# fpgaB35.net
KiCad netlist of a schematic drawn in Altium Designer
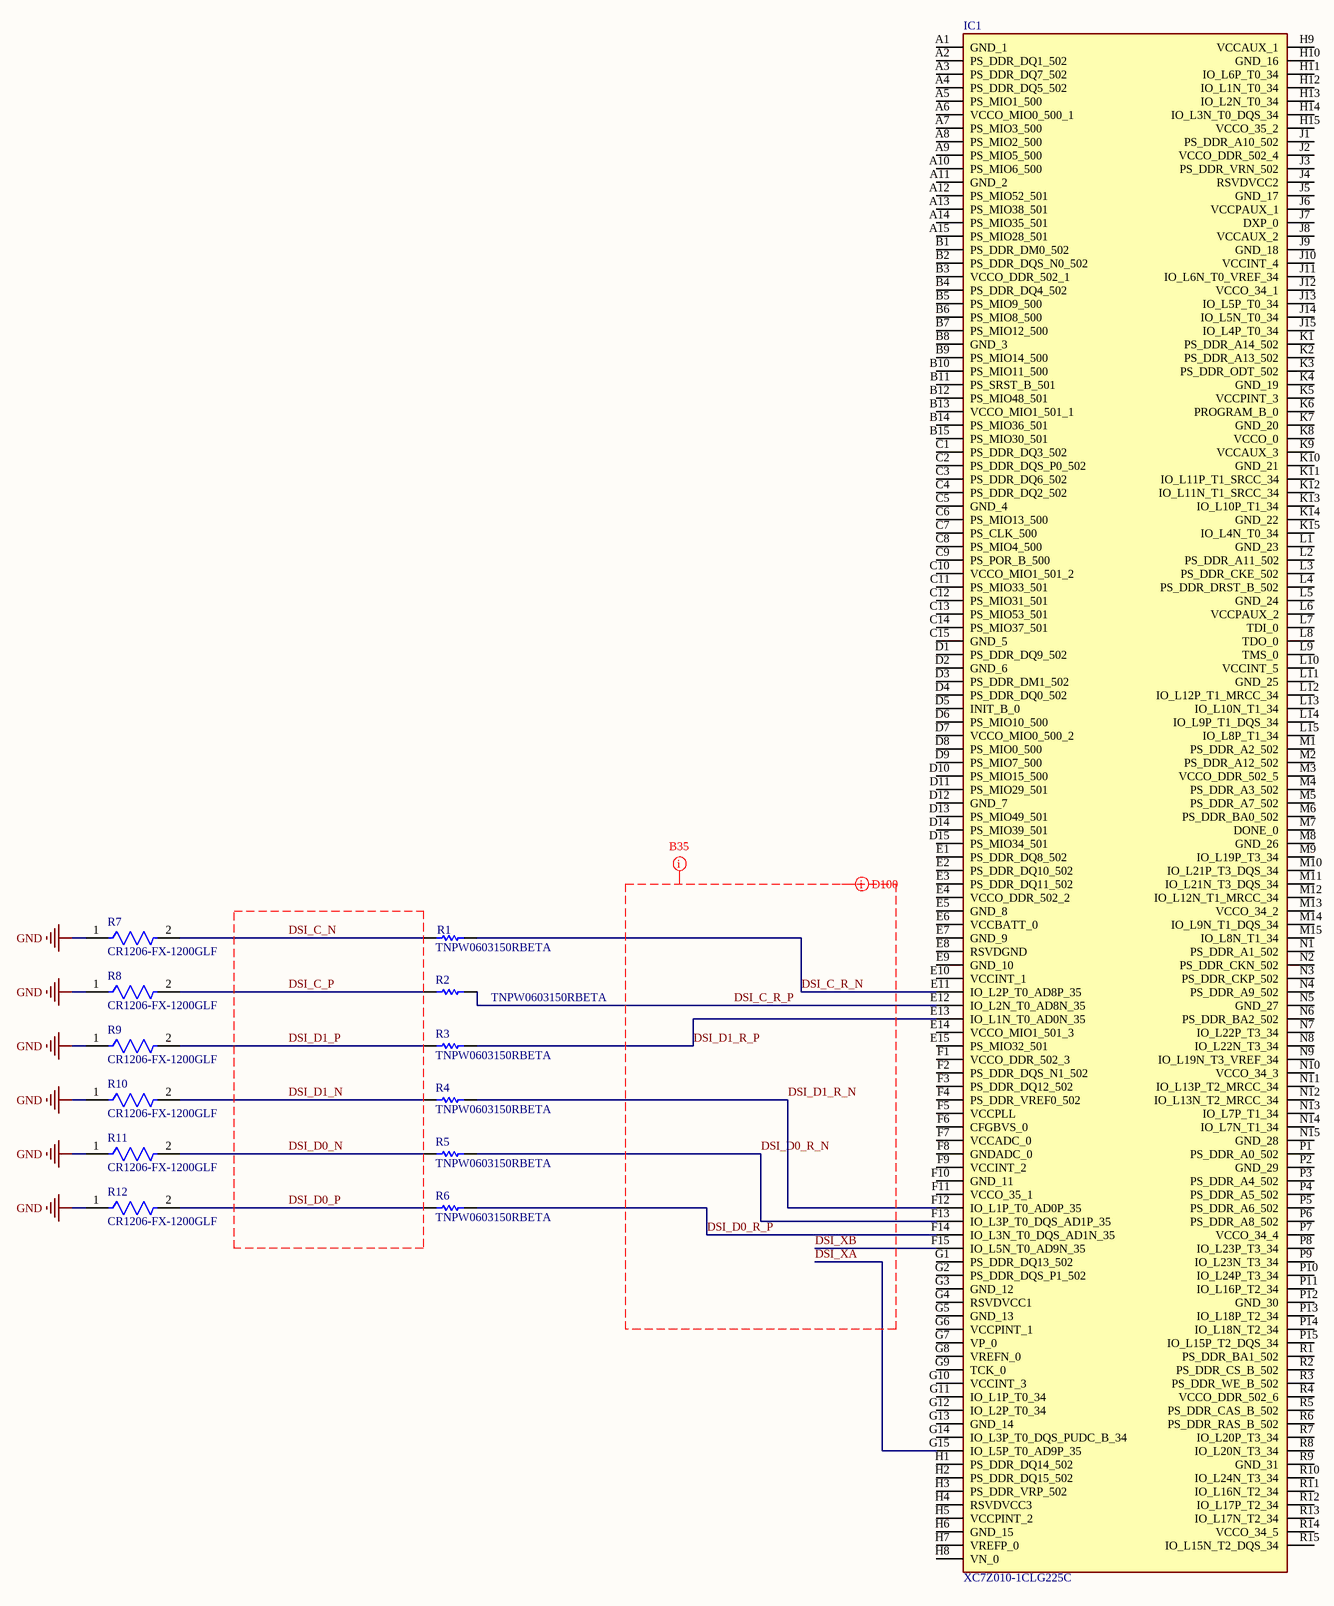
[diagram p0: fpgaB35.SchDoc]

(export (version "E")
  (design (tool "Eeschema 10.0.6"))
  (components
    (comp (ref "IC1")
      (value "XC7Z010-1CLG225C")
      (footprint "SamacSys:BGA225C80P15X15_1300X1300X140")
      (description "Integrated Circuit")
      (fields (field (name "MOUSER PART NUMBER") "217-XC7Z010-1CLG225C"))
      (libsource (lib "*") (part "XC7Z010-1CLG225C"))
    )
    (comp (ref "R1")
      (value "TNPW0603150RBETA")
      (footprint "RESC1609X55X30NL10T20")
      (fields (field (name "MANUFACTURER") "Vishay Dale"))
      (libsource (lib "Altium Content Vault") (part "RES"))
    )
    (comp (ref "R2")
      (value "TNPW0603150RBETA")
      (footprint "RESC1609X55X30NL10T20")
      (fields (field (name "MANUFACTURER") "Vishay Dale"))
      (libsource (lib "Altium Content Vault") (part "RES"))
    )
    (comp (ref "R3")
      (value "TNPW0603150RBETA")
      (footprint "RESC1609X55X30NL10T20")
      (fields (field (name "MANUFACTURER") "Vishay Dale"))
      (libsource (lib "Altium Content Vault") (part "RES"))
    )
    (comp (ref "R4")
      (value "TNPW0603150RBETA")
      (footprint "RESC1609X55X30NL10T20")
      (fields (field (name "MANUFACTURER") "Vishay Dale"))
      (libsource (lib "Altium Content Vault") (part "RES"))
    )
    (comp (ref "R5")
      (value "TNPW0603150RBETA")
      (footprint "RESC1609X55X30NL10T20")
      (fields (field (name "MANUFACTURER") "Vishay Dale"))
      (libsource (lib "Altium Content Vault") (part "RES"))
    )
    (comp (ref "R6")
      (value "TNPW0603150RBETA")
      (footprint "RESC1609X55X30NL10T20")
      (fields (field (name "MANUFACTURER") "Vishay Dale"))
      (libsource (lib "Altium Content Vault") (part "RES"))
    )
    (comp (ref "R7")
      (value "CR1206-FX-1200GLF")
      (footprint "FP-CR1206-MFG")
      (description "Thick Film Chip Resistors 1206 120Ω 0.25W 1% 100ppm/°C")
      (fields (field (name "TOLERANCE") "1%"))
      (libsource (lib "Altium Content Vault") (part "1029c3af85768c4190bb7ad29bc67b5"))
    )
    (comp (ref "R8")
      (value "CR1206-FX-1200GLF")
      (footprint "FP-CR1206-MFG")
      (description "Thick Film Chip Resistors 1206 120Ω 0.25W 1% 100ppm/°C")
      (fields (field (name "TOLERANCE") "1%"))
      (libsource (lib "Altium Content Vault") (part "1029c3af85768c4190bb7ad29bc67b5"))
    )
    (comp (ref "R9")
      (value "CR1206-FX-1200GLF")
      (footprint "FP-CR1206-MFG")
      (description "Thick Film Chip Resistors 1206 120Ω 0.25W 1% 100ppm/°C")
      (fields (field (name "TOLERANCE") "1%"))
      (libsource (lib "Altium Content Vault") (part "1029c3af85768c4190bb7ad29bc67b5"))
    )
    (comp (ref "R10")
      (value "CR1206-FX-1200GLF")
      (footprint "FP-CR1206-MFG")
      (description "Thick Film Chip Resistors 1206 120Ω 0.25W 1% 100ppm/°C")
      (fields (field (name "TOLERANCE") "1%"))
      (libsource (lib "Altium Content Vault") (part "1029c3af85768c4190bb7ad29bc67b5"))
    )
    (comp (ref "R11")
      (value "CR1206-FX-1200GLF")
      (footprint "FP-CR1206-MFG")
      (description "Thick Film Chip Resistors 1206 120Ω 0.25W 1% 100ppm/°C")
      (fields (field (name "TOLERANCE") "1%"))
      (libsource (lib "Altium Content Vault") (part "1029c3af85768c4190bb7ad29bc67b5"))
    )
    (comp (ref "R12")
      (value "CR1206-FX-1200GLF")
      (footprint "FP-CR1206-MFG")
      (description "Thick Film Chip Resistors 1206 120Ω 0.25W 1% 100ppm/°C")
      (fields (field (name "TOLERANCE") "1%"))
      (libsource (lib "Altium Content Vault") (part "1029c3af85768c4190bb7ad29bc67b5"))
    )
  )
  (nets
    (net (code "1") (name "/DSI_C_N") (class "Default")
      (node (ref "R1") (pin "1") (pinfunction "1_1") (pintype "passive"))
      (node (ref "R7") (pin "2") (pinfunction "2_2") (pintype "passive"))
    )
    (net (code "2") (name "/DSI_C_P") (class "Default")
      (node (ref "R2") (pin "1") (pinfunction "1_1") (pintype "passive"))
      (node (ref "R8") (pin "2") (pinfunction "2_2") (pintype "passive"))
    )
    (net (code "3") (name "/DSI_C_R_N") (class "Default")
      (node (ref "IC1") (pin "E11") (pinfunction "IO_L2P_T0_AD8P_35_E11") (pintype "passive"))
      (node (ref "R1") (pin "2") (pinfunction "2_2") (pintype "passive"))
    )
    (net (code "4") (name "/DSI_C_R_P") (class "Default")
      (node (ref "IC1") (pin "E12") (pinfunction "IO_L2N_T0_AD8N_35_E12") (pintype "passive"))
      (node (ref "R2") (pin "2") (pinfunction "2_2") (pintype "passive"))
    )
    (net (code "5") (name "/DSI_D0_N") (class "Default")
      (node (ref "R11") (pin "2") (pinfunction "2_2") (pintype "passive"))
      (node (ref "R5") (pin "1") (pinfunction "1_1") (pintype "passive"))
    )
    (net (code "6") (name "/DSI_D0_P") (class "Default")
      (node (ref "R12") (pin "2") (pinfunction "2_2") (pintype "passive"))
      (node (ref "R6") (pin "1") (pinfunction "1_1") (pintype "passive"))
    )
    (net (code "7") (name "/DSI_D0_R_N") (class "Default")
      (node (ref "IC1") (pin "F13") (pinfunction "IO_L3P_T0_DQS_AD1P_35_F13") (pintype "passive"))
      (node (ref "R5") (pin "2") (pinfunction "2_2") (pintype "passive"))
    )
    (net (code "8") (name "/DSI_D0_R_P") (class "Default")
      (node (ref "IC1") (pin "F14") (pinfunction "IO_L3N_T0_DQS_AD1N_35_F14") (pintype "passive"))
      (node (ref "R6") (pin "2") (pinfunction "2_2") (pintype "passive"))
    )
    (net (code "9") (name "/DSI_D1_N") (class "Default")
      (node (ref "R10") (pin "2") (pinfunction "2_2") (pintype "passive"))
      (node (ref "R4") (pin "1") (pinfunction "1_1") (pintype "passive"))
    )
    (net (code "10") (name "/DSI_D1_P") (class "Default")
      (node (ref "R3") (pin "1") (pinfunction "1_1") (pintype "passive"))
      (node (ref "R9") (pin "2") (pinfunction "2_2") (pintype "passive"))
    )
    (net (code "11") (name "/DSI_D1_R_N") (class "Default")
      (node (ref "IC1") (pin "F12") (pinfunction "IO_L1P_T0_AD0P_35_F12") (pintype "passive"))
      (node (ref "R4") (pin "2") (pinfunction "2_2") (pintype "passive"))
    )
    (net (code "12") (name "/DSI_D1_R_P") (class "Default")
      (node (ref "IC1") (pin "E13") (pinfunction "IO_L1N_T0_AD0N_35_E13") (pintype "passive"))
      (node (ref "R3") (pin "2") (pinfunction "2_2") (pintype "passive"))
    )
    (net (code "13") (name "/DSI_XA") (class "Default")
      (node (ref "IC1") (pin "G15") (pinfunction "IO_L5P_T0_AD9P_35_G15") (pintype "passive"))
    )
    (net (code "14") (name "/DSI_XB") (class "Default")
      (node (ref "IC1") (pin "F15") (pinfunction "IO_L5N_T0_AD9N_35_F15") (pintype "passive"))
    )
    (net (code "15") (name "GND") (class "Default")
      (node (ref "R10") (pin "1") (pinfunction "1_1") (pintype "passive"))
      (node (ref "R11") (pin "1") (pinfunction "1_1") (pintype "passive"))
      (node (ref "R12") (pin "1") (pinfunction "1_1") (pintype "passive"))
      (node (ref "R7") (pin "1") (pinfunction "1_1") (pintype "passive"))
      (node (ref "R8") (pin "1") (pinfunction "1_1") (pintype "passive"))
      (node (ref "R9") (pin "1") (pinfunction "1_1") (pintype "passive"))
    )
    (net (code "16") (name "unconnected-(IC1-CFGBVS_0-PadF6)") (class "Default")
      (node (ref "IC1") (pin "F6") (pinfunction "CFGBVS_0_F6") (pintype "passive"))
    )
    (net (code "17") (name "unconnected-(IC1-DONE_0-PadM7)") (class "Default")
      (node (ref "IC1") (pin "M7") (pinfunction "DONE_0_M7") (pintype "passive"))
    )
    (net (code "18") (name "unconnected-(IC1-DXP_0-PadJ7)") (class "Default")
      (node (ref "IC1") (pin "J7") (pinfunction "DXP_0_J7") (pintype "passive"))
    )
    (net (code "19") (name "unconnected-(IC1-GNDADC_0-PadF8)") (class "Default")
      (node (ref "IC1") (pin "F8") (pinfunction "GNDADC_0_F8") (pintype "passive"))
    )
    (net (code "20") (name "unconnected-(IC1-GND_1-PadA1)") (class "Default")
      (node (ref "IC1") (pin "A1") (pinfunction "GND_1_A1") (pintype "passive"))
    )
    (net (code "21") (name "unconnected-(IC1-GND_2-PadA11)") (class "Default")
      (node (ref "IC1") (pin "A11") (pinfunction "GND_2_A11") (pintype "passive"))
    )
    (net (code "22") (name "unconnected-(IC1-GND_3-PadB8)") (class "Default")
      (node (ref "IC1") (pin "B8") (pinfunction "GND_3_B8") (pintype "passive"))
    )
    (net (code "23") (name "unconnected-(IC1-GND_4-PadC5)") (class "Default")
      (node (ref "IC1") (pin "C5") (pinfunction "GND_4_C5") (pintype "passive"))
    )
    (net (code "24") (name "unconnected-(IC1-GND_5-PadC15)") (class "Default")
      (node (ref "IC1") (pin "C15") (pinfunction "GND_5_C15") (pintype "passive"))
    )
    (net (code "25") (name "unconnected-(IC1-GND_6-PadD2)") (class "Default")
      (node (ref "IC1") (pin "D2") (pinfunction "GND_6_D2") (pintype "passive"))
    )
    (net (code "26") (name "unconnected-(IC1-GND_7-PadD12)") (class "Default")
      (node (ref "IC1") (pin "D12") (pinfunction "GND_7_D12") (pintype "passive"))
    )
    (net (code "27") (name "unconnected-(IC1-GND_8-PadE5)") (class "Default")
      (node (ref "IC1") (pin "E5") (pinfunction "GND_8_E5") (pintype "passive"))
    )
    (net (code "28") (name "unconnected-(IC1-GND_9-PadE7)") (class "Default")
      (node (ref "IC1") (pin "E7") (pinfunction "GND_9_E7") (pintype "passive"))
    )
    (net (code "29") (name "unconnected-(IC1-GND_10-PadE9)") (class "Default")
      (node (ref "IC1") (pin "E9") (pinfunction "GND_10_E9") (pintype "passive"))
    )
    (net (code "30") (name "unconnected-(IC1-GND_11-PadF10)") (class "Default")
      (node (ref "IC1") (pin "F10") (pinfunction "GND_11_F10") (pintype "passive"))
    )
    (net (code "31") (name "unconnected-(IC1-GND_12-PadG3)") (class "Default")
      (node (ref "IC1") (pin "G3") (pinfunction "GND_12_G3") (pintype "passive"))
    )
    (net (code "32") (name "unconnected-(IC1-GND_13-PadG5)") (class "Default")
      (node (ref "IC1") (pin "G5") (pinfunction "GND_13_G5") (pintype "passive"))
    )
    (net (code "33") (name "unconnected-(IC1-GND_14-PadG13)") (class "Default")
      (node (ref "IC1") (pin "G13") (pinfunction "GND_14_G13") (pintype "passive"))
    )
    (net (code "34") (name "unconnected-(IC1-GND_15-PadH6)") (class "Default")
      (node (ref "IC1") (pin "H6") (pinfunction "GND_15_H6") (pintype "passive"))
    )
    (net (code "35") (name "unconnected-(IC1-GND_16-PadH10)") (class "Default")
      (node (ref "IC1") (pin "H10") (pinfunction "GND_16_H10") (pintype "passive"))
    )
    (net (code "36") (name "unconnected-(IC1-GND_17-PadJ5)") (class "Default")
      (node (ref "IC1") (pin "J5") (pinfunction "GND_17_J5") (pintype "passive"))
    )
    (net (code "37") (name "unconnected-(IC1-GND_18-PadJ9)") (class "Default")
      (node (ref "IC1") (pin "J9") (pinfunction "GND_18_J9") (pintype "passive"))
    )
    (net (code "38") (name "unconnected-(IC1-GND_19-PadK4)") (class "Default")
      (node (ref "IC1") (pin "K4") (pinfunction "GND_19_K4") (pintype "passive"))
    )
    (net (code "39") (name "unconnected-(IC1-GND_20-PadK7)") (class "Default")
      (node (ref "IC1") (pin "K7") (pinfunction "GND_20_K7") (pintype "passive"))
    )
    (net (code "40") (name "unconnected-(IC1-GND_21-PadK10)") (class "Default")
      (node (ref "IC1") (pin "K10") (pinfunction "GND_21_K10") (pintype "passive"))
    )
    (net (code "41") (name "unconnected-(IC1-GND_22-PadK14)") (class "Default")
      (node (ref "IC1") (pin "K14") (pinfunction "GND_22_K14") (pintype "passive"))
    )
    (net (code "42") (name "unconnected-(IC1-GND_23-PadL1)") (class "Default")
      (node (ref "IC1") (pin "L1") (pinfunction "GND_23_L1") (pintype "passive"))
    )
    (net (code "43") (name "unconnected-(IC1-GND_24-PadL5)") (class "Default")
      (node (ref "IC1") (pin "L5") (pinfunction "GND_24_L5") (pintype "passive"))
    )
    (net (code "44") (name "unconnected-(IC1-GND_25-PadL11)") (class "Default")
      (node (ref "IC1") (pin "L11") (pinfunction "GND_25_L11") (pintype "passive"))
    )
    (net (code "45") (name "unconnected-(IC1-GND_26-PadM8)") (class "Default")
      (node (ref "IC1") (pin "M8") (pinfunction "GND_26_M8") (pintype "passive"))
    )
    (net (code "46") (name "unconnected-(IC1-GND_27-PadN5)") (class "Default")
      (node (ref "IC1") (pin "N5") (pinfunction "GND_27_N5") (pintype "passive"))
    )
    (net (code "47") (name "unconnected-(IC1-GND_28-PadN15)") (class "Default")
      (node (ref "IC1") (pin "N15") (pinfunction "GND_28_N15") (pintype "passive"))
    )
    (net (code "48") (name "unconnected-(IC1-GND_29-PadP2)") (class "Default")
      (node (ref "IC1") (pin "P2") (pinfunction "GND_29_P2") (pintype "passive"))
    )
    (net (code "49") (name "unconnected-(IC1-GND_30-PadP12)") (class "Default")
      (node (ref "IC1") (pin "P12") (pinfunction "GND_30_P12") (pintype "passive"))
    )
    (net (code "50") (name "unconnected-(IC1-GND_31-PadR9)") (class "Default")
      (node (ref "IC1") (pin "R9") (pinfunction "GND_31_R9") (pintype "passive"))
    )
    (net (code "51") (name "unconnected-(IC1-INIT_B_0-PadD5)") (class "Default")
      (node (ref "IC1") (pin "D5") (pinfunction "INIT_B_0_D5") (pintype "passive"))
    )
    (net (code "52") (name "unconnected-(IC1-IO_L1N_T0_34-PadH12)") (class "Default")
      (node (ref "IC1") (pin "H12") (pinfunction "IO_L1N_T0_34_H12") (pintype "passive"))
    )
    (net (code "53") (name "unconnected-(IC1-IO_L1P_T0_34-PadG11)") (class "Default")
      (node (ref "IC1") (pin "G11") (pinfunction "IO_L1P_T0_34_G11") (pintype "passive"))
    )
    (net (code "54") (name "unconnected-(IC1-IO_L2N_T0_34-PadH13)") (class "Default")
      (node (ref "IC1") (pin "H13") (pinfunction "IO_L2N_T0_34_H13") (pintype "passive"))
    )
    (net (code "55") (name "unconnected-(IC1-IO_L2P_T0_34-PadG12)") (class "Default")
      (node (ref "IC1") (pin "G12") (pinfunction "IO_L2P_T0_34_G12") (pintype "passive"))
    )
    (net (code "56") (name "unconnected-(IC1-IO_L3N_T0_DQS_34-PadH14)") (class "Default")
      (node (ref "IC1") (pin "H14") (pinfunction "IO_L3N_T0_DQS_34_H14") (pintype "passive"))
    )
    (net (code "57") (name "unconnected-(IC1-IO_L3P_T0_DQS_PUDC_B_34-PadG14)") (class "Default")
      (node (ref "IC1") (pin "G14") (pinfunction "IO_L3P_T0_DQS_PUDC_B_34_G14") (pintype "passive"))
    )
    (net (code "58") (name "unconnected-(IC1-IO_L4N_T0_34-PadK15)") (class "Default")
      (node (ref "IC1") (pin "K15") (pinfunction "IO_L4N_T0_34_K15") (pintype "passive"))
    )
    (net (code "59") (name "unconnected-(IC1-IO_L4P_T0_34-PadJ15)") (class "Default")
      (node (ref "IC1") (pin "J15") (pinfunction "IO_L4P_T0_34_J15") (pintype "passive"))
    )
    (net (code "60") (name "unconnected-(IC1-IO_L5N_T0_34-PadJ14)") (class "Default")
      (node (ref "IC1") (pin "J14") (pinfunction "IO_L5N_T0_34_J14") (pintype "passive"))
    )
    (net (code "61") (name "unconnected-(IC1-IO_L5P_T0_34-PadJ13)") (class "Default")
      (node (ref "IC1") (pin "J13") (pinfunction "IO_L5P_T0_34_J13") (pintype "passive"))
    )
    (net (code "62") (name "unconnected-(IC1-IO_L6N_T0_VREF_34-PadJ11)") (class "Default")
      (node (ref "IC1") (pin "J11") (pinfunction "IO_L6N_T0_VREF_34_J11") (pintype "passive"))
    )
    (net (code "63") (name "unconnected-(IC1-IO_L6P_T0_34-PadH11)") (class "Default")
      (node (ref "IC1") (pin "H11") (pinfunction "IO_L6P_T0_34_H11") (pintype "passive"))
    )
    (net (code "64") (name "unconnected-(IC1-IO_L7N_T1_34-PadN14)") (class "Default")
      (node (ref "IC1") (pin "N14") (pinfunction "IO_L7N_T1_34_N14") (pintype "passive"))
    )
    (net (code "65") (name "unconnected-(IC1-IO_L7P_T1_34-PadN13)") (class "Default")
      (node (ref "IC1") (pin "N13") (pinfunction "IO_L7P_T1_34_N13") (pintype "passive"))
    )
    (net (code "66") (name "unconnected-(IC1-IO_L8N_T1_34-PadM15)") (class "Default")
      (node (ref "IC1") (pin "M15") (pinfunction "IO_L8N_T1_34_M15") (pintype "passive"))
    )
    (net (code "67") (name "unconnected-(IC1-IO_L8P_T1_34-PadL15)") (class "Default")
      (node (ref "IC1") (pin "L15") (pinfunction "IO_L8P_T1_34_L15") (pintype "passive"))
    )
    (net (code "68") (name "unconnected-(IC1-IO_L9N_T1_DQS_34-PadM14)") (class "Default")
      (node (ref "IC1") (pin "M14") (pinfunction "IO_L9N_T1_DQS_34_M14") (pintype "passive"))
    )
    (net (code "69") (name "unconnected-(IC1-IO_L9P_T1_DQS_34-PadL14)") (class "Default")
      (node (ref "IC1") (pin "L14") (pinfunction "IO_L9P_T1_DQS_34_L14") (pintype "passive"))
    )
    (net (code "70") (name "unconnected-(IC1-IO_L10N_T1_34-PadL13)") (class "Default")
      (node (ref "IC1") (pin "L13") (pinfunction "IO_L10N_T1_34_L13") (pintype "passive"))
    )
    (net (code "71") (name "unconnected-(IC1-IO_L10P_T1_34-PadK13)") (class "Default")
      (node (ref "IC1") (pin "K13") (pinfunction "IO_L10P_T1_34_K13") (pintype "passive"))
    )
    (net (code "72") (name "unconnected-(IC1-IO_L11N_T1_SRCC_34-PadK12)") (class "Default")
      (node (ref "IC1") (pin "K12") (pinfunction "IO_L11N_T1_SRCC_34_K12") (pintype "passive"))
    )
    (net (code "73") (name "unconnected-(IC1-IO_L11P_T1_SRCC_34-PadK11)") (class "Default")
      (node (ref "IC1") (pin "K11") (pinfunction "IO_L11P_T1_SRCC_34_K11") (pintype "passive"))
    )
    (net (code "74") (name "unconnected-(IC1-IO_L12N_T1_MRCC_34-PadM12)") (class "Default")
      (node (ref "IC1") (pin "M12") (pinfunction "IO_L12N_T1_MRCC_34_M12") (pintype "passive"))
    )
    (net (code "75") (name "unconnected-(IC1-IO_L12P_T1_MRCC_34-PadL12)") (class "Default")
      (node (ref "IC1") (pin "L12") (pinfunction "IO_L12P_T1_MRCC_34_L12") (pintype "passive"))
    )
    (net (code "76") (name "unconnected-(IC1-IO_L13N_T2_MRCC_34-PadN12)") (class "Default")
      (node (ref "IC1") (pin "N12") (pinfunction "IO_L13N_T2_MRCC_34_N12") (pintype "passive"))
    )
    (net (code "77") (name "unconnected-(IC1-IO_L13P_T2_MRCC_34-PadN11)") (class "Default")
      (node (ref "IC1") (pin "N11") (pinfunction "IO_L13P_T2_MRCC_34_N11") (pintype "passive"))
    )
    (net (code "78") (name "unconnected-(IC1-IO_L15N_T2_DQS_34-PadR15)") (class "Default")
      (node (ref "IC1") (pin "R15") (pinfunction "IO_L15N_T2_DQS_34_R15") (pintype "passive"))
    )
    (net (code "79") (name "unconnected-(IC1-IO_L15P_T2_DQS_34-PadP15)") (class "Default")
      (node (ref "IC1") (pin "P15") (pinfunction "IO_L15P_T2_DQS_34_P15") (pintype "passive"))
    )
    (net (code "80") (name "unconnected-(IC1-IO_L16N_T2_34-PadR11)") (class "Default")
      (node (ref "IC1") (pin "R11") (pinfunction "IO_L16N_T2_34_R11") (pintype "passive"))
    )
    (net (code "81") (name "unconnected-(IC1-IO_L16P_T2_34-PadP11)") (class "Default")
      (node (ref "IC1") (pin "P11") (pinfunction "IO_L16P_T2_34_P11") (pintype "passive"))
    )
    (net (code "82") (name "unconnected-(IC1-IO_L17N_T2_34-PadR13)") (class "Default")
      (node (ref "IC1") (pin "R13") (pinfunction "IO_L17N_T2_34_R13") (pintype "passive"))
    )
    (net (code "83") (name "unconnected-(IC1-IO_L17P_T2_34-PadR12)") (class "Default")
      (node (ref "IC1") (pin "R12") (pinfunction "IO_L17P_T2_34_R12") (pintype "passive"))
    )
    (net (code "84") (name "unconnected-(IC1-IO_L18N_T2_34-PadP14)") (class "Default")
      (node (ref "IC1") (pin "P14") (pinfunction "IO_L18N_T2_34_P14") (pintype "passive"))
    )
    (net (code "85") (name "unconnected-(IC1-IO_L18P_T2_34-PadP13)") (class "Default")
      (node (ref "IC1") (pin "P13") (pinfunction "IO_L18P_T2_34_P13") (pintype "passive"))
    )
    (net (code "86") (name "unconnected-(IC1-IO_L19N_T3_VREF_34-PadN9)") (class "Default")
      (node (ref "IC1") (pin "N9") (pinfunction "IO_L19N_T3_VREF_34_N9") (pintype "passive"))
    )
    (net (code "87") (name "unconnected-(IC1-IO_L19P_T3_34-PadM9)") (class "Default")
      (node (ref "IC1") (pin "M9") (pinfunction "IO_L19P_T3_34_M9") (pintype "passive"))
    )
    (net (code "88") (name "unconnected-(IC1-IO_L20N_T3_34-PadR8)") (class "Default")
      (node (ref "IC1") (pin "R8") (pinfunction "IO_L20N_T3_34_R8") (pintype "passive"))
    )
    (net (code "89") (name "unconnected-(IC1-IO_L20P_T3_34-PadR7)") (class "Default")
      (node (ref "IC1") (pin "R7") (pinfunction "IO_L20P_T3_34_R7") (pintype "passive"))
    )
    (net (code "90") (name "unconnected-(IC1-IO_L21N_T3_DQS_34-PadM11)") (class "Default")
      (node (ref "IC1") (pin "M11") (pinfunction "IO_L21N_T3_DQS_34_M11") (pintype "passive"))
    )
    (net (code "91") (name "unconnected-(IC1-IO_L21P_T3_DQS_34-PadM10)") (class "Default")
      (node (ref "IC1") (pin "M10") (pinfunction "IO_L21P_T3_DQS_34_M10") (pintype "passive"))
    )
    (net (code "92") (name "unconnected-(IC1-IO_L22N_T3_34-PadN8)") (class "Default")
      (node (ref "IC1") (pin "N8") (pinfunction "IO_L22N_T3_34_N8") (pintype "passive"))
    )
    (net (code "93") (name "unconnected-(IC1-IO_L22P_T3_34-PadN7)") (class "Default")
      (node (ref "IC1") (pin "N7") (pinfunction "IO_L22P_T3_34_N7") (pintype "passive"))
    )
    (net (code "94") (name "unconnected-(IC1-IO_L23N_T3_34-PadP9)") (class "Default")
      (node (ref "IC1") (pin "P9") (pinfunction "IO_L23N_T3_34_P9") (pintype "passive"))
    )
    (net (code "95") (name "unconnected-(IC1-IO_L23P_T3_34-PadP8)") (class "Default")
      (node (ref "IC1") (pin "P8") (pinfunction "IO_L23P_T3_34_P8") (pintype "passive"))
    )
    (net (code "96") (name "unconnected-(IC1-IO_L24N_T3_34-PadR10)") (class "Default")
      (node (ref "IC1") (pin "R10") (pinfunction "IO_L24N_T3_34_R10") (pintype "passive"))
    )
    (net (code "97") (name "unconnected-(IC1-IO_L24P_T3_34-PadP10)") (class "Default")
      (node (ref "IC1") (pin "P10") (pinfunction "IO_L24P_T3_34_P10") (pintype "passive"))
    )
    (net (code "98") (name "unconnected-(IC1-PROGRAM_B_0-PadK6)") (class "Default")
      (node (ref "IC1") (pin "K6") (pinfunction "PROGRAM_B_0_K6") (pintype "passive"))
    )
    (net (code "99") (name "unconnected-(IC1-PS_CLK_500-PadC7)") (class "Default")
      (node (ref "IC1") (pin "C7") (pinfunction "PS_CLK_500_C7") (pintype "passive"))
    )
    (net (code "100") (name "unconnected-(IC1-PS_DDR_A0_502-PadP1)") (class "Default")
      (node (ref "IC1") (pin "P1") (pinfunction "PS_DDR_A0_502_P1") (pintype "passive"))
    )
    (net (code "101") (name "unconnected-(IC1-PS_DDR_A1_502-PadN1)") (class "Default")
      (node (ref "IC1") (pin "N1") (pinfunction "PS_DDR_A1_502_N1") (pintype "passive"))
    )
    (net (code "102") (name "unconnected-(IC1-PS_DDR_A2_502-PadM1)") (class "Default")
      (node (ref "IC1") (pin "M1") (pinfunction "PS_DDR_A2_502_M1") (pintype "passive"))
    )
    (net (code "103") (name "unconnected-(IC1-PS_DDR_A3_502-PadM4)") (class "Default")
      (node (ref "IC1") (pin "M4") (pinfunction "PS_DDR_A3_502_M4") (pintype "passive"))
    )
    (net (code "104") (name "unconnected-(IC1-PS_DDR_A4_502-PadP3)") (class "Default")
      (node (ref "IC1") (pin "P3") (pinfunction "PS_DDR_A4_502_P3") (pintype "passive"))
    )
    (net (code "105") (name "unconnected-(IC1-PS_DDR_A5_502-PadP4)") (class "Default")
      (node (ref "IC1") (pin "P4") (pinfunction "PS_DDR_A5_502_P4") (pintype "passive"))
    )
    (net (code "106") (name "unconnected-(IC1-PS_DDR_A6_502-PadP5)") (class "Default")
      (node (ref "IC1") (pin "P5") (pinfunction "PS_DDR_A6_502_P5") (pintype "passive"))
    )
    (net (code "107") (name "unconnected-(IC1-PS_DDR_A7_502-PadM5)") (class "Default")
      (node (ref "IC1") (pin "M5") (pinfunction "PS_DDR_A7_502_M5") (pintype "passive"))
    )
    (net (code "108") (name "unconnected-(IC1-PS_DDR_A8_502-PadP6)") (class "Default")
      (node (ref "IC1") (pin "P6") (pinfunction "PS_DDR_A8_502_P6") (pintype "passive"))
    )
    (net (code "109") (name "unconnected-(IC1-PS_DDR_A9_502-PadN4)") (class "Default")
      (node (ref "IC1") (pin "N4") (pinfunction "PS_DDR_A9_502_N4") (pintype "passive"))
    )
    (net (code "110") (name "unconnected-(IC1-PS_DDR_A10_502-PadJ1)") (class "Default")
      (node (ref "IC1") (pin "J1") (pinfunction "PS_DDR_A10_502_J1") (pintype "passive"))
    )
    (net (code "111") (name "unconnected-(IC1-PS_DDR_A11_502-PadL2)") (class "Default")
      (node (ref "IC1") (pin "L2") (pinfunction "PS_DDR_A11_502_L2") (pintype "passive"))
    )
    (net (code "112") (name "unconnected-(IC1-PS_DDR_A12_502-PadM2)") (class "Default")
      (node (ref "IC1") (pin "M2") (pinfunction "PS_DDR_A12_502_M2") (pintype "passive"))
    )
    (net (code "113") (name "unconnected-(IC1-PS_DDR_A13_502-PadK2)") (class "Default")
      (node (ref "IC1") (pin "K2") (pinfunction "PS_DDR_A13_502_K2") (pintype "passive"))
    )
    (net (code "114") (name "unconnected-(IC1-PS_DDR_A14_502-PadK1)") (class "Default")
      (node (ref "IC1") (pin "K1") (pinfunction "PS_DDR_A14_502_K1") (pintype "passive"))
    )
    (net (code "115") (name "unconnected-(IC1-PS_DDR_BA0_502-PadM6)") (class "Default")
      (node (ref "IC1") (pin "M6") (pinfunction "PS_DDR_BA0_502_M6") (pintype "passive"))
    )
    (net (code "116") (name "unconnected-(IC1-PS_DDR_BA1_502-PadR1)") (class "Default")
      (node (ref "IC1") (pin "R1") (pinfunction "PS_DDR_BA1_502_R1") (pintype "passive"))
    )
    (net (code "117") (name "unconnected-(IC1-PS_DDR_BA2_502-PadN6)") (class "Default")
      (node (ref "IC1") (pin "N6") (pinfunction "PS_DDR_BA2_502_N6") (pintype "passive"))
    )
    (net (code "118") (name "unconnected-(IC1-PS_DDR_CAS_B_502-PadR5)") (class "Default")
      (node (ref "IC1") (pin "R5") (pinfunction "PS_DDR_CAS_B_502_R5") (pintype "passive"))
    )
    (net (code "119") (name "unconnected-(IC1-PS_DDR_CKE_502-PadL3)") (class "Default")
      (node (ref "IC1") (pin "L3") (pinfunction "PS_DDR_CKE_502_L3") (pintype "passive"))
    )
    (net (code "120") (name "unconnected-(IC1-PS_DDR_CKN_502-PadN2)") (class "Default")
      (node (ref "IC1") (pin "N2") (pinfunction "PS_DDR_CKN_502_N2") (pintype "passive"))
    )
    (net (code "121") (name "unconnected-(IC1-PS_DDR_CKP_502-PadN3)") (class "Default")
      (node (ref "IC1") (pin "N3") (pinfunction "PS_DDR_CKP_502_N3") (pintype "passive"))
    )
    (net (code "122") (name "unconnected-(IC1-PS_DDR_CS_B_502-PadR2)") (class "Default")
      (node (ref "IC1") (pin "R2") (pinfunction "PS_DDR_CS_B_502_R2") (pintype "passive"))
    )
    (net (code "123") (name "unconnected-(IC1-PS_DDR_DM0_502-PadB1)") (class "Default")
      (node (ref "IC1") (pin "B1") (pinfunction "PS_DDR_DM0_502_B1") (pintype "passive"))
    )
    (net (code "124") (name "unconnected-(IC1-PS_DDR_DM1_502-PadD3)") (class "Default")
      (node (ref "IC1") (pin "D3") (pinfunction "PS_DDR_DM1_502_D3") (pintype "passive"))
    )
    (net (code "125") (name "unconnected-(IC1-PS_DDR_DQ0_502-PadD4)") (class "Default")
      (node (ref "IC1") (pin "D4") (pinfunction "PS_DDR_DQ0_502_D4") (pintype "passive"))
    )
    (net (code "126") (name "unconnected-(IC1-PS_DDR_DQ1_502-PadA2)") (class "Default")
      (node (ref "IC1") (pin "A2") (pinfunction "PS_DDR_DQ1_502_A2") (pintype "passive"))
    )
    (net (code "127") (name "unconnected-(IC1-PS_DDR_DQ2_502-PadC4)") (class "Default")
      (node (ref "IC1") (pin "C4") (pinfunction "PS_DDR_DQ2_502_C4") (pintype "passive"))
    )
    (net (code "128") (name "unconnected-(IC1-PS_DDR_DQ3_502-PadC1)") (class "Default")
      (node (ref "IC1") (pin "C1") (pinfunction "PS_DDR_DQ3_502_C1") (pintype "passive"))
    )
    (net (code "129") (name "unconnected-(IC1-PS_DDR_DQ4_502-PadB4)") (class "Default")
      (node (ref "IC1") (pin "B4") (pinfunction "PS_DDR_DQ4_502_B4") (pintype "passive"))
    )
    (net (code "130") (name "unconnected-(IC1-PS_DDR_DQ5_502-PadA4)") (class "Default")
      (node (ref "IC1") (pin "A4") (pinfunction "PS_DDR_DQ5_502_A4") (pintype "passive"))
    )
    (net (code "131") (name "unconnected-(IC1-PS_DDR_DQ6_502-PadC3)") (class "Default")
      (node (ref "IC1") (pin "C3") (pinfunction "PS_DDR_DQ6_502_C3") (pintype "passive"))
    )
    (net (code "132") (name "unconnected-(IC1-PS_DDR_DQ7_502-PadA3)") (class "Default")
      (node (ref "IC1") (pin "A3") (pinfunction "PS_DDR_DQ7_502_A3") (pintype "passive"))
    )
    (net (code "133") (name "unconnected-(IC1-PS_DDR_DQ8_502-PadE1)") (class "Default")
      (node (ref "IC1") (pin "E1") (pinfunction "PS_DDR_DQ8_502_E1") (pintype "passive"))
    )
    (net (code "134") (name "unconnected-(IC1-PS_DDR_DQ9_502-PadD1)") (class "Default")
      (node (ref "IC1") (pin "D1") (pinfunction "PS_DDR_DQ9_502_D1") (pintype "passive"))
    )
    (net (code "135") (name "unconnected-(IC1-PS_DDR_DQ10_502-PadE2)") (class "Default")
      (node (ref "IC1") (pin "E2") (pinfunction "PS_DDR_DQ10_502_E2") (pintype "passive"))
    )
    (net (code "136") (name "unconnected-(IC1-PS_DDR_DQ11_502-PadE3)") (class "Default")
      (node (ref "IC1") (pin "E3") (pinfunction "PS_DDR_DQ11_502_E3") (pintype "passive"))
    )
    (net (code "137") (name "unconnected-(IC1-PS_DDR_DQ12_502-PadF3)") (class "Default")
      (node (ref "IC1") (pin "F3") (pinfunction "PS_DDR_DQ12_502_F3") (pintype "passive"))
    )
    (net (code "138") (name "unconnected-(IC1-PS_DDR_DQ13_502-PadG1)") (class "Default")
      (node (ref "IC1") (pin "G1") (pinfunction "PS_DDR_DQ13_502_G1") (pintype "passive"))
    )
    (net (code "139") (name "unconnected-(IC1-PS_DDR_DQ14_502-PadH1)") (class "Default")
      (node (ref "IC1") (pin "H1") (pinfunction "PS_DDR_DQ14_502_H1") (pintype "passive"))
    )
    (net (code "140") (name "unconnected-(IC1-PS_DDR_DQ15_502-PadH2)") (class "Default")
      (node (ref "IC1") (pin "H2") (pinfunction "PS_DDR_DQ15_502_H2") (pintype "passive"))
    )
    (net (code "141") (name "unconnected-(IC1-PS_DDR_DQS_N0_502-PadB2)") (class "Default")
      (node (ref "IC1") (pin "B2") (pinfunction "PS_DDR_DQS_N0_502_B2") (pintype "passive"))
    )
    (net (code "142") (name "unconnected-(IC1-PS_DDR_DQS_N1_502-PadF2)") (class "Default")
      (node (ref "IC1") (pin "F2") (pinfunction "PS_DDR_DQS_N1_502_F2") (pintype "passive"))
    )
    (net (code "143") (name "unconnected-(IC1-PS_DDR_DQS_P0_502-PadC2)") (class "Default")
      (node (ref "IC1") (pin "C2") (pinfunction "PS_DDR_DQS_P0_502_C2") (pintype "passive"))
    )
    (net (code "144") (name "unconnected-(IC1-PS_DDR_DQS_P1_502-PadG2)") (class "Default")
      (node (ref "IC1") (pin "G2") (pinfunction "PS_DDR_DQS_P1_502_G2") (pintype "passive"))
    )
    (net (code "145") (name "unconnected-(IC1-PS_DDR_DRST_B_502-PadL4)") (class "Default")
      (node (ref "IC1") (pin "L4") (pinfunction "PS_DDR_DRST_B_502_L4") (pintype "passive"))
    )
    (net (code "146") (name "unconnected-(IC1-PS_DDR_ODT_502-PadK3)") (class "Default")
      (node (ref "IC1") (pin "K3") (pinfunction "PS_DDR_ODT_502_K3") (pintype "passive"))
    )
    (net (code "147") (name "unconnected-(IC1-PS_DDR_RAS_B_502-PadR6)") (class "Default")
      (node (ref "IC1") (pin "R6") (pinfunction "PS_DDR_RAS_B_502_R6") (pintype "passive"))
    )
    (net (code "148") (name "unconnected-(IC1-PS_DDR_VREF0_502-PadF4)") (class "Default")
      (node (ref "IC1") (pin "F4") (pinfunction "PS_DDR_VREF0_502_F4") (pintype "passive"))
    )
    (net (code "149") (name "unconnected-(IC1-PS_DDR_VRN_502-PadJ3)") (class "Default")
      (node (ref "IC1") (pin "J3") (pinfunction "PS_DDR_VRN_502_J3") (pintype "passive"))
    )
    (net (code "150") (name "unconnected-(IC1-PS_DDR_VRP_502-PadH3)") (class "Default")
      (node (ref "IC1") (pin "H3") (pinfunction "PS_DDR_VRP_502_H3") (pintype "passive"))
    )
    (net (code "151") (name "unconnected-(IC1-PS_DDR_WE_B_502-PadR3)") (class "Default")
      (node (ref "IC1") (pin "R3") (pinfunction "PS_DDR_WE_B_502_R3") (pintype "passive"))
    )
    (net (code "152") (name "unconnected-(IC1-PS_MIO0_500-PadD8)") (class "Default")
      (node (ref "IC1") (pin "D8") (pinfunction "PS_MIO0_500_D8") (pintype "passive"))
    )
    (net (code "153") (name "unconnected-(IC1-PS_MIO1_500-PadA5)") (class "Default")
      (node (ref "IC1") (pin "A5") (pinfunction "PS_MIO1_500_A5") (pintype "passive"))
    )
    (net (code "154") (name "unconnected-(IC1-PS_MIO2_500-PadA8)") (class "Default")
      (node (ref "IC1") (pin "A8") (pinfunction "PS_MIO2_500_A8") (pintype "passive"))
    )
    (net (code "155") (name "unconnected-(IC1-PS_MIO3_500-PadA7)") (class "Default")
      (node (ref "IC1") (pin "A7") (pinfunction "PS_MIO3_500_A7") (pintype "passive"))
    )
    (net (code "156") (name "unconnected-(IC1-PS_MIO4_500-PadC8)") (class "Default")
      (node (ref "IC1") (pin "C8") (pinfunction "PS_MIO4_500_C8") (pintype "passive"))
    )
    (net (code "157") (name "unconnected-(IC1-PS_MIO5_500-PadA9)") (class "Default")
      (node (ref "IC1") (pin "A9") (pinfunction "PS_MIO5_500_A9") (pintype "passive"))
    )
    (net (code "158") (name "unconnected-(IC1-PS_MIO6_500-PadA10)") (class "Default")
      (node (ref "IC1") (pin "A10") (pinfunction "PS_MIO6_500_A10") (pintype "passive"))
    )
    (net (code "159") (name "unconnected-(IC1-PS_MIO7_500-PadD9)") (class "Default")
      (node (ref "IC1") (pin "D9") (pinfunction "PS_MIO7_500_D9") (pintype "passive"))
    )
    (net (code "160") (name "unconnected-(IC1-PS_MIO8_500-PadB6)") (class "Default")
      (node (ref "IC1") (pin "B6") (pinfunction "PS_MIO8_500_B6") (pintype "passive"))
    )
    (net (code "161") (name "unconnected-(IC1-PS_MIO9_500-PadB5)") (class "Default")
      (node (ref "IC1") (pin "B5") (pinfunction "PS_MIO9_500_B5") (pintype "passive"))
    )
    (net (code "162") (name "unconnected-(IC1-PS_MIO10_500-PadD6)") (class "Default")
      (node (ref "IC1") (pin "D6") (pinfunction "PS_MIO10_500_D6") (pintype "passive"))
    )
    (net (code "163") (name "unconnected-(IC1-PS_MIO11_500-PadB10)") (class "Default")
      (node (ref "IC1") (pin "B10") (pinfunction "PS_MIO11_500_B10") (pintype "passive"))
    )
    (net (code "164") (name "unconnected-(IC1-PS_MIO12_500-PadB7)") (class "Default")
      (node (ref "IC1") (pin "B7") (pinfunction "PS_MIO12_500_B7") (pintype "passive"))
    )
    (net (code "165") (name "unconnected-(IC1-PS_MIO13_500-PadC6)") (class "Default")
      (node (ref "IC1") (pin "C6") (pinfunction "PS_MIO13_500_C6") (pintype "passive"))
    )
    (net (code "166") (name "unconnected-(IC1-PS_MIO14_500-PadB9)") (class "Default")
      (node (ref "IC1") (pin "B9") (pinfunction "PS_MIO14_500_B9") (pintype "passive"))
    )
    (net (code "167") (name "unconnected-(IC1-PS_MIO15_500-PadD10)") (class "Default")
      (node (ref "IC1") (pin "D10") (pinfunction "PS_MIO15_500_D10") (pintype "passive"))
    )
    (net (code "168") (name "unconnected-(IC1-PS_MIO28_501-PadA15)") (class "Default")
      (node (ref "IC1") (pin "A15") (pinfunction "PS_MIO28_501_A15") (pintype "passive"))
    )
    (net (code "169") (name "unconnected-(IC1-PS_MIO29_501-PadD11)") (class "Default")
      (node (ref "IC1") (pin "D11") (pinfunction "PS_MIO29_501_D11") (pintype "passive"))
    )
    (net (code "170") (name "unconnected-(IC1-PS_MIO30_501-PadB15)") (class "Default")
      (node (ref "IC1") (pin "B15") (pinfunction "PS_MIO30_501_B15") (pintype "passive"))
    )
    (net (code "171") (name "unconnected-(IC1-PS_MIO31_501-PadC12)") (class "Default")
      (node (ref "IC1") (pin "C12") (pinfunction "PS_MIO31_501_C12") (pintype "passive"))
    )
    (net (code "172") (name "unconnected-(IC1-PS_MIO32_501-PadE15)") (class "Default")
      (node (ref "IC1") (pin "E15") (pinfunction "PS_MIO32_501_E15") (pintype "passive"))
    )
    (net (code "173") (name "unconnected-(IC1-PS_MIO33_501-PadC11)") (class "Default")
      (node (ref "IC1") (pin "C11") (pinfunction "PS_MIO33_501_C11") (pintype "passive"))
    )
    (net (code "174") (name "unconnected-(IC1-PS_MIO34_501-PadD15)") (class "Default")
      (node (ref "IC1") (pin "D15") (pinfunction "PS_MIO34_501_D15") (pintype "passive"))
    )
    (net (code "175") (name "unconnected-(IC1-PS_MIO35_501-PadA14)") (class "Default")
      (node (ref "IC1") (pin "A14") (pinfunction "PS_MIO35_501_A14") (pintype "passive"))
    )
    (net (code "176") (name "unconnected-(IC1-PS_MIO36_501-PadB14)") (class "Default")
      (node (ref "IC1") (pin "B14") (pinfunction "PS_MIO36_501_B14") (pintype "passive"))
    )
    (net (code "177") (name "unconnected-(IC1-PS_MIO37_501-PadC14)") (class "Default")
      (node (ref "IC1") (pin "C14") (pinfunction "PS_MIO37_501_C14") (pintype "passive"))
    )
    (net (code "178") (name "unconnected-(IC1-PS_MIO38_501-PadA13)") (class "Default")
      (node (ref "IC1") (pin "A13") (pinfunction "PS_MIO38_501_A13") (pintype "passive"))
    )
    (net (code "179") (name "unconnected-(IC1-PS_MIO39_501-PadD14)") (class "Default")
      (node (ref "IC1") (pin "D14") (pinfunction "PS_MIO39_501_D14") (pintype "passive"))
    )
    (net (code "180") (name "unconnected-(IC1-PS_MIO48_501-PadB12)") (class "Default")
      (node (ref "IC1") (pin "B12") (pinfunction "PS_MIO48_501_B12") (pintype "passive"))
    )
    (net (code "181") (name "unconnected-(IC1-PS_MIO49_501-PadD13)") (class "Default")
      (node (ref "IC1") (pin "D13") (pinfunction "PS_MIO49_501_D13") (pintype "passive"))
    )
    (net (code "182") (name "unconnected-(IC1-PS_MIO52_501-PadA12)") (class "Default")
      (node (ref "IC1") (pin "A12") (pinfunction "PS_MIO52_501_A12") (pintype "passive"))
    )
    (net (code "183") (name "unconnected-(IC1-PS_MIO53_501-PadC13)") (class "Default")
      (node (ref "IC1") (pin "C13") (pinfunction "PS_MIO53_501_C13") (pintype "passive"))
    )
    (net (code "184") (name "unconnected-(IC1-PS_POR_B_500-PadC9)") (class "Default")
      (node (ref "IC1") (pin "C9") (pinfunction "PS_POR_B_500_C9") (pintype "passive"))
    )
    (net (code "185") (name "unconnected-(IC1-PS_SRST_B_501-PadB11)") (class "Default")
      (node (ref "IC1") (pin "B11") (pinfunction "PS_SRST_B_501_B11") (pintype "passive"))
    )
    (net (code "186") (name "unconnected-(IC1-RSVDGND-PadE8)") (class "Default")
      (node (ref "IC1") (pin "E8") (pinfunction "RSVDGND_E8") (pintype "passive"))
    )
    (net (code "187") (name "unconnected-(IC1-RSVDVCC1-PadG4)") (class "Default")
      (node (ref "IC1") (pin "G4") (pinfunction "RSVDVCC1_G4") (pintype "passive"))
    )
    (net (code "188") (name "unconnected-(IC1-RSVDVCC2-PadJ4)") (class "Default")
      (node (ref "IC1") (pin "J4") (pinfunction "RSVDVCC2_J4") (pintype "passive"))
    )
    (net (code "189") (name "unconnected-(IC1-RSVDVCC3-PadH4)") (class "Default")
      (node (ref "IC1") (pin "H4") (pinfunction "RSVDVCC3_H4") (pintype "passive"))
    )
    (net (code "190") (name "unconnected-(IC1-TCK_0-PadG9)") (class "Default")
      (node (ref "IC1") (pin "G9") (pinfunction "TCK_0_G9") (pintype "passive"))
    )
    (net (code "191") (name "unconnected-(IC1-TDI_0-PadL7)") (class "Default")
      (node (ref "IC1") (pin "L7") (pinfunction "TDI_0_L7") (pintype "passive"))
    )
    (net (code "192") (name "unconnected-(IC1-TDO_0-PadL8)") (class "Default")
      (node (ref "IC1") (pin "L8") (pinfunction "TDO_0_L8") (pintype "passive"))
    )
    (net (code "193") (name "unconnected-(IC1-TMS_0-PadL9)") (class "Default")
      (node (ref "IC1") (pin "L9") (pinfunction "TMS_0_L9") (pintype "passive"))
    )
    (net (code "194") (name "unconnected-(IC1-VCCADC_0-PadF7)") (class "Default")
      (node (ref "IC1") (pin "F7") (pinfunction "VCCADC_0_F7") (pintype "passive"))
    )
    (net (code "195") (name "unconnected-(IC1-VCCAUX_1-PadH9)") (class "Default")
      (node (ref "IC1") (pin "H9") (pinfunction "VCCAUX_1_H9") (pintype "passive"))
    )
    (net (code "196") (name "unconnected-(IC1-VCCAUX_2-PadJ8)") (class "Default")
      (node (ref "IC1") (pin "J8") (pinfunction "VCCAUX_2_J8") (pintype "passive"))
    )
    (net (code "197") (name "unconnected-(IC1-VCCAUX_3-PadK9)") (class "Default")
      (node (ref "IC1") (pin "K9") (pinfunction "VCCAUX_3_K9") (pintype "passive"))
    )
    (net (code "198") (name "unconnected-(IC1-VCCBATT_0-PadE6)") (class "Default")
      (node (ref "IC1") (pin "E6") (pinfunction "VCCBATT_0_E6") (pintype "passive"))
    )
    (net (code "199") (name "unconnected-(IC1-VCCINT_1-PadE10)") (class "Default")
      (node (ref "IC1") (pin "E10") (pinfunction "VCCINT_1_E10") (pintype "passive"))
    )
    (net (code "200") (name "unconnected-(IC1-VCCINT_2-PadF9)") (class "Default")
      (node (ref "IC1") (pin "F9") (pinfunction "VCCINT_2_F9") (pintype "passive"))
    )
    (net (code "201") (name "unconnected-(IC1-VCCINT_3-PadG10)") (class "Default")
      (node (ref "IC1") (pin "G10") (pinfunction "VCCINT_3_G10") (pintype "passive"))
    )
    (net (code "202") (name "unconnected-(IC1-VCCINT_4-PadJ10)") (class "Default")
      (node (ref "IC1") (pin "J10") (pinfunction "VCCINT_4_J10") (pintype "passive"))
    )
    (net (code "203") (name "unconnected-(IC1-VCCINT_5-PadL10)") (class "Default")
      (node (ref "IC1") (pin "L10") (pinfunction "VCCINT_5_L10") (pintype "passive"))
    )
    (net (code "204") (name "unconnected-(IC1-VCCO_0-PadK8)") (class "Default")
      (node (ref "IC1") (pin "K8") (pinfunction "VCCO_0_K8") (pintype "passive"))
    )
    (net (code "205") (name "unconnected-(IC1-VCCO_34_1-PadJ12)") (class "Default")
      (node (ref "IC1") (pin "J12") (pinfunction "VCCO_34_1_J12") (pintype "passive"))
    )
    (net (code "206") (name "unconnected-(IC1-VCCO_34_2-PadM13)") (class "Default")
      (node (ref "IC1") (pin "M13") (pinfunction "VCCO_34_2_M13") (pintype "passive"))
    )
    (net (code "207") (name "unconnected-(IC1-VCCO_34_3-PadN10)") (class "Default")
      (node (ref "IC1") (pin "N10") (pinfunction "VCCO_34_3_N10") (pintype "passive"))
    )
    (net (code "208") (name "unconnected-(IC1-VCCO_34_4-PadP7)") (class "Default")
      (node (ref "IC1") (pin "P7") (pinfunction "VCCO_34_4_P7") (pintype "passive"))
    )
    (net (code "209") (name "unconnected-(IC1-VCCO_34_5-PadR14)") (class "Default")
      (node (ref "IC1") (pin "R14") (pinfunction "VCCO_34_5_R14") (pintype "passive"))
    )
    (net (code "210") (name "unconnected-(IC1-VCCO_35_1-PadF11)") (class "Default")
      (node (ref "IC1") (pin "F11") (pinfunction "VCCO_35_1_F11") (pintype "passive"))
    )
    (net (code "211") (name "unconnected-(IC1-VCCO_35_2-PadH15)") (class "Default")
      (node (ref "IC1") (pin "H15") (pinfunction "VCCO_35_2_H15") (pintype "passive"))
    )
    (net (code "212") (name "unconnected-(IC1-VCCO_DDR_502_1-PadB3)") (class "Default")
      (node (ref "IC1") (pin "B3") (pinfunction "VCCO_DDR_502_1_B3") (pintype "passive"))
    )
    (net (code "213") (name "unconnected-(IC1-VCCO_DDR_502_2-PadE4)") (class "Default")
      (node (ref "IC1") (pin "E4") (pinfunction "VCCO_DDR_502_2_E4") (pintype "passive"))
    )
    (net (code "214") (name "unconnected-(IC1-VCCO_DDR_502_3-PadF1)") (class "Default")
      (node (ref "IC1") (pin "F1") (pinfunction "VCCO_DDR_502_3_F1") (pintype "passive"))
    )
    (net (code "215") (name "unconnected-(IC1-VCCO_DDR_502_4-PadJ2)") (class "Default")
      (node (ref "IC1") (pin "J2") (pinfunction "VCCO_DDR_502_4_J2") (pintype "passive"))
    )
    (net (code "216") (name "unconnected-(IC1-VCCO_DDR_502_5-PadM3)") (class "Default")
      (node (ref "IC1") (pin "M3") (pinfunction "VCCO_DDR_502_5_M3") (pintype "passive"))
    )
    (net (code "217") (name "unconnected-(IC1-VCCO_DDR_502_6-PadR4)") (class "Default")
      (node (ref "IC1") (pin "R4") (pinfunction "VCCO_DDR_502_6_R4") (pintype "passive"))
    )
    (net (code "218") (name "unconnected-(IC1-VCCO_MIO0_500_1-PadA6)") (class "Default")
      (node (ref "IC1") (pin "A6") (pinfunction "VCCO_MIO0_500_1_A6") (pintype "passive"))
    )
    (net (code "219") (name "unconnected-(IC1-VCCO_MIO0_500_2-PadD7)") (class "Default")
      (node (ref "IC1") (pin "D7") (pinfunction "VCCO_MIO0_500_2_D7") (pintype "passive"))
    )
    (net (code "220") (name "unconnected-(IC1-VCCO_MIO1_501_1-PadB13)") (class "Default")
      (node (ref "IC1") (pin "B13") (pinfunction "VCCO_MIO1_501_1_B13") (pintype "passive"))
    )
    (net (code "221") (name "unconnected-(IC1-VCCO_MIO1_501_2-PadC10)") (class "Default")
      (node (ref "IC1") (pin "C10") (pinfunction "VCCO_MIO1_501_2_C10") (pintype "passive"))
    )
    (net (code "222") (name "unconnected-(IC1-VCCO_MIO1_501_3-PadE14)") (class "Default")
      (node (ref "IC1") (pin "E14") (pinfunction "VCCO_MIO1_501_3_E14") (pintype "passive"))
    )
    (net (code "223") (name "unconnected-(IC1-VCCPAUX_1-PadJ6)") (class "Default")
      (node (ref "IC1") (pin "J6") (pinfunction "VCCPAUX_1_J6") (pintype "passive"))
    )
    (net (code "224") (name "unconnected-(IC1-VCCPAUX_2-PadL6)") (class "Default")
      (node (ref "IC1") (pin "L6") (pinfunction "VCCPAUX_2_L6") (pintype "passive"))
    )
    (net (code "225") (name "unconnected-(IC1-VCCPINT_1-PadG6)") (class "Default")
      (node (ref "IC1") (pin "G6") (pinfunction "VCCPINT_1_G6") (pintype "passive"))
    )
    (net (code "226") (name "unconnected-(IC1-VCCPINT_2-PadH5)") (class "Default")
      (node (ref "IC1") (pin "H5") (pinfunction "VCCPINT_2_H5") (pintype "passive"))
    )
    (net (code "227") (name "unconnected-(IC1-VCCPINT_3-PadK5)") (class "Default")
      (node (ref "IC1") (pin "K5") (pinfunction "VCCPINT_3_K5") (pintype "passive"))
    )
    (net (code "228") (name "unconnected-(IC1-VCCPLL-PadF5)") (class "Default")
      (node (ref "IC1") (pin "F5") (pinfunction "VCCPLL_F5") (pintype "passive"))
    )
    (net (code "229") (name "unconnected-(IC1-VN_0-PadH8)") (class "Default")
      (node (ref "IC1") (pin "H8") (pinfunction "VN_0_H8") (pintype "passive"))
    )
    (net (code "230") (name "unconnected-(IC1-VP_0-PadG7)") (class "Default")
      (node (ref "IC1") (pin "G7") (pinfunction "VP_0_G7") (pintype "passive"))
    )
    (net (code "231") (name "unconnected-(IC1-VREFN_0-PadG8)") (class "Default")
      (node (ref "IC1") (pin "G8") (pinfunction "VREFN_0_G8") (pintype "passive"))
    )
    (net (code "232") (name "unconnected-(IC1-VREFP_0-PadH7)") (class "Default")
      (node (ref "IC1") (pin "H7") (pinfunction "VREFP_0_H7") (pintype "passive"))
    )
  )
)
